# L6203.net
KiCad netlist of a schematic drawn in Altium Designer
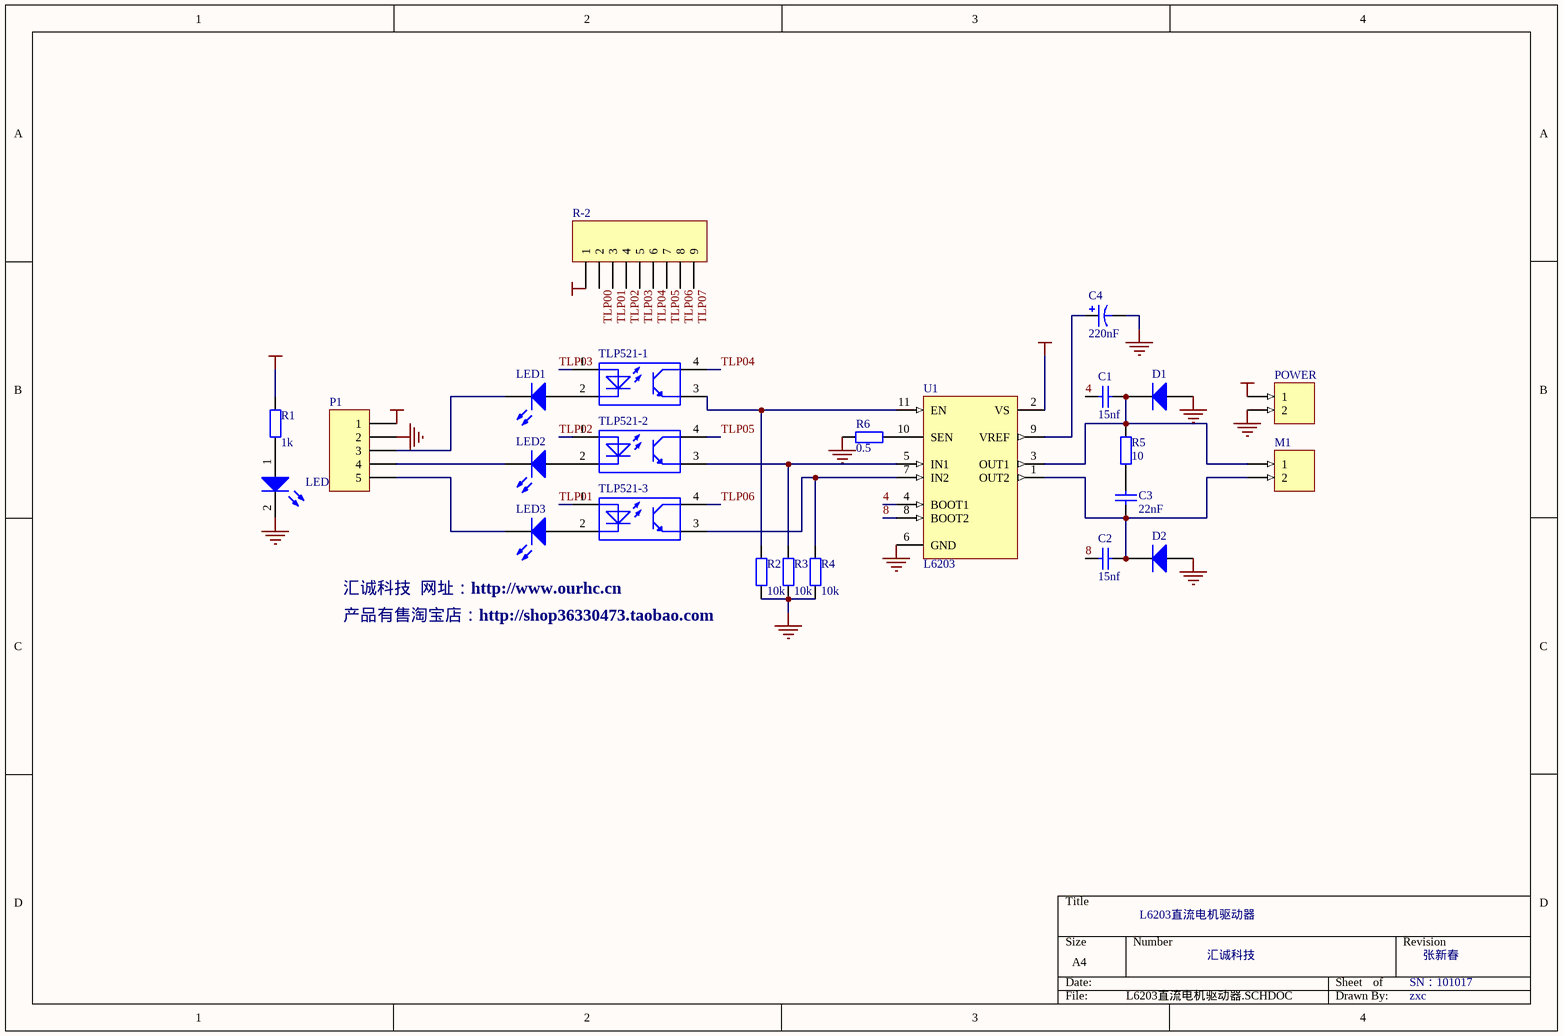
[diagram p0: L6203直流电机驱动器.SCHDOC]

(export (version "E")
  (design (tool "Eeschema 10.0.6"))
  (components
    (comp (ref "C1")
      (value "15nf")
      (footprint "CPDR")
      (description "Capacitor")
      (fields (field (name "PUBLISHER") "Altium Limited"))
      (libsource (lib "Miscellaneous Devices") (part "Cap"))
    )
    (comp (ref "C2")
      (value "15nf")
      (footprint "CPDR")
      (description "Capacitor")
      (fields (field (name "PUBLISHER") "Altium Limited"))
      (libsource (lib "Miscellaneous Devices") (part "Cap"))
    )
    (comp (ref "C3")
      (value "22nF")
      (footprint "CPDR")
      (description "Capacitor")
      (fields (field (name "PUBLISHER") "Altium Limited"))
      (libsource (lib "Miscellaneous Devices") (part "Cap"))
    )
    (comp (ref "C4")
      (value "220nF")
      (footprint "C-DJ-4")
      (description "Polarized Capacitor (Surface Mount)")
      (fields (field (name "PUBLISHER") "Altium Limited"))
      (libsource (lib "Miscellaneous Devices") (part "Cap Pol3"))
    )
    (comp (ref "D1")
      (value "1N4007")
      (footprint "ZCDZL")
      (description "1 Amp General Purpose Rectifier")
      (fields (field (name "PUBLISHER") "Altium Limited"))
      (libsource (lib "Miscellaneous Devices") (part "Diode 1N4007"))
    )
    (comp (ref "D2")
      (value "1N4007")
      (footprint "ZCDZL")
      (description "1 Amp General Purpose Rectifier")
      (fields (field (name "PUBLISHER") "Altium Limited"))
      (libsource (lib "Miscellaneous Devices") (part "Diode 1N4007"))
    )
    (comp (ref "LED")
      (value "LED")
      (footprint "CPDR")
      (description "发光二极管")
      (fields (field (name "PUBLISHER") "Altium Limited"))
      (libsource (lib "zxcourhc") (part "LED"))
    )
    (comp (ref "LED1")
      (value "~")
      (footprint "HDR1X2")
      (description "Typical BLUE SiC LED")
      (fields (field (name "PUBLISHER") "Altium Limited"))
      (libsource (lib "Miscellaneous Devices") (part "LED3"))
    )
    (comp (ref "LED2")
      (value "~")
      (footprint "HDR1X2")
      (description "Typical BLUE SiC LED")
      (fields (field (name "PUBLISHER") "Altium Limited"))
      (libsource (lib "Miscellaneous Devices") (part "LED3"))
    )
    (comp (ref "LED3")
      (value "~")
      (footprint "HDR1X2")
      (description "Typical BLUE SiC LED")
      (fields (field (name "PUBLISHER") "Altium Limited"))
      (libsource (lib "Miscellaneous Devices") (part "LED3"))
    )
    (comp (ref "M1")
      (value "~")
      (footprint "JK128_2")
      (description "Header, 2-Pin")
      (fields (field (name "PUBLISHER") "Altium Limited"))
      (libsource (lib "Miscellaneous Connectors") (part "MHDR1X2"))
    )
    (comp (ref "P1")
      (value "PZ_5")
      (footprint "HDR-5")
      (description "排针——5")
      (fields (field (name "PUBLISHER") "Altium Limited"))
      (libsource (lib "zxcourhc") (part "PZ_5"))
    )
    (comp (ref "POWER")
      (value "~")
      (footprint "JK128_2")
      (description "Header, 2-Pin")
      (fields (field (name "PUBLISHER") "Altium Limited"))
      (libsource (lib "Miscellaneous Connectors") (part "MHDR1X2"))
    )
    (comp (ref "R-2")
      (value "~")
      (footprint "HDR1X9")
      (description "Header, 9-Pin")
      (fields (field (name "PUBLISHER") "Altium Limited"))
      (libsource (lib "Miscellaneous Connectors") (part "Header 9"))
    )
    (comp (ref "R1")
      (value "1k")
      (footprint "zxcourhc:TP-0805-R")
      (description "电阻")
      (fields (field (name "Comment") "Res") (field (name "PUBLISHER") "Altium Limited"))
      (libsource (lib "zxcourhc") (part "Res"))
    )
    (comp (ref "R2")
      (value "10k")
      (footprint "zxcourhc:TP-0805-R")
      (description "电阻")
      (fields (field (name "Comment") "Res") (field (name "PUBLISHER") "Altium Limited"))
      (libsource (lib "zxcourhc") (part "Res"))
    )
    (comp (ref "R3")
      (value "10k")
      (footprint "zxcourhc:TP-0805-R")
      (description "电阻")
      (fields (field (name "Comment") "Res") (field (name "PUBLISHER") "Altium Limited"))
      (libsource (lib "zxcourhc") (part "Res"))
    )
    (comp (ref "R4")
      (value "10k")
      (footprint "zxcourhc:TP-0805-R")
      (description "电阻")
      (fields (field (name "Comment") "Res") (field (name "PUBLISHER") "Altium Limited"))
      (libsource (lib "zxcourhc") (part "Res"))
    )
    (comp (ref "R5")
      (value "10")
      (footprint "ZCDZL")
      (description "电阻")
      (fields (field (name "Comment") "Res") (field (name "PUBLISHER") "Altium Limited"))
      (libsource (lib "zxcourhc") (part "Res"))
    )
    (comp (ref "R6")
      (value "0.5")
      (footprint "ZCDZL")
      (description "电阻")
      (fields (field (name "Comment") "Res") (field (name "PUBLISHER") "Altium Limited"))
      (libsource (lib "") (part "Res_1"))
    )
    (comp (ref "TLP521-1") (value "~") (footprint "DIP-4") (libsource (lib "MyInt_Lib") (part "TLP521-1")))
    (comp (ref "TLP521-2") (value "~") (footprint "DIP-4") (libsource (lib "MyInt_Lib") (part "TLP521-1")))
    (comp (ref "TLP521-3") (value "~") (footprint "DIP-4") (libsource (lib "MyInt_Lib") (part "TLP521-1")))
    (comp (ref "U1")
      (value "L6203")
      (footprint "LMD18200")
      (description "DMOS Full Bridge Driver")
      (fields (field (name "PUBLISHER") "Altium Limited"))
      (libsource (lib "ST Interface DC Motor Controller") (part "L6203"))
    )
  )
  (nets
    (net (code "1") (name "+5V") (class "Default")
      (node (ref "P1") (pin "1") (pinfunction "1_1") (pintype "passive"))
      (node (ref "R-2") (pin "1") (pinfunction "1_1") (pintype "passive"))
      (node (ref "R1") (pin "1") (pinfunction "1_1") (pintype "passive"))
    )
    (net (code "2") (name "/4") (class "Default")
      (node (ref "C1") (pin "2") (pinfunction "2_2") (pintype "passive"))
      (node (ref "U1") (pin "4") (pinfunction "BOOT1_4") (pintype "input"))
    )
    (net (code "3") (name "/8") (class "Default")
      (node (ref "C2") (pin "2") (pinfunction "2_2") (pintype "passive"))
      (node (ref "U1") (pin "8") (pinfunction "BOOT2_8") (pintype "input"))
    )
    (net (code "4") (name "/TLP00") (class "Default")
      (node (ref "R-2") (pin "2") (pinfunction "2_2") (pintype "passive"))
    )
    (net (code "5") (name "/TLP01") (class "Default")
      (node (ref "R-2") (pin "3") (pinfunction "3_3") (pintype "passive"))
      (node (ref "TLP521-3") (pin "1") (pinfunction "1_1") (pintype "passive"))
    )
    (net (code "6") (name "/TLP02") (class "Default")
      (node (ref "R-2") (pin "4") (pinfunction "4_4") (pintype "passive"))
      (node (ref "TLP521-2") (pin "1") (pinfunction "1_1") (pintype "passive"))
    )
    (net (code "7") (name "/TLP03") (class "Default")
      (node (ref "R-2") (pin "5") (pinfunction "5_5") (pintype "passive"))
      (node (ref "TLP521-1") (pin "1") (pinfunction "1_1") (pintype "passive"))
    )
    (net (code "8") (name "/TLP04") (class "Default")
      (node (ref "R-2") (pin "6") (pinfunction "6_6") (pintype "passive"))
      (node (ref "TLP521-1") (pin "4") (pinfunction "4_4") (pintype "passive"))
    )
    (net (code "9") (name "/TLP05") (class "Default")
      (node (ref "R-2") (pin "7") (pinfunction "7_7") (pintype "passive"))
      (node (ref "TLP521-2") (pin "4") (pinfunction "4_4") (pintype "passive"))
    )
    (net (code "10") (name "/TLP06") (class "Default")
      (node (ref "R-2") (pin "8") (pinfunction "8_8") (pintype "passive"))
      (node (ref "TLP521-3") (pin "4") (pinfunction "4_4") (pintype "passive"))
    )
    (net (code "11") (name "/TLP07") (class "Default")
      (node (ref "R-2") (pin "9") (pinfunction "9_9") (pintype "passive"))
    )
    (net (code "12") (name "GND") (class "Default")
      (node (ref "C4") (pin "2") (pinfunction "2_2") (pintype "passive"))
      (node (ref "D1") (pin "1") (pinfunction "A_1") (pintype "passive"))
      (node (ref "D2") (pin "1") (pinfunction "A_1") (pintype "passive"))
      (node (ref "LED") (pin "2") (pinfunction "K_2") (pintype "passive"))
      (node (ref "P1") (pin "2") (pinfunction "2_2") (pintype "passive"))
      (node (ref "POWER") (pin "2") (pinfunction "2_2") (pintype "input"))
      (node (ref "R2") (pin "2") (pinfunction "2_2") (pintype "passive"))
      (node (ref "R3") (pin "2") (pinfunction "2_2") (pintype "passive"))
      (node (ref "R4") (pin "2") (pinfunction "2_2") (pintype "passive"))
      (node (ref "R6") (pin "1") (pinfunction "1_1") (pintype "passive"))
      (node (ref "U1") (pin "6") (pinfunction "GND_6") (pintype "power_in"))
    )
    (net (code "13") (name "Net-(C3-Pad1)") (class "Default")
      (node (ref "C3") (pin "1") (pinfunction "1_1") (pintype "passive"))
      (node (ref "R5") (pin "2") (pinfunction "2_2") (pintype "passive"))
    )
    (net (code "14") (name "Net-(D1-K)") (class "Default")
      (node (ref "C1") (pin "1") (pinfunction "1_1") (pintype "passive"))
      (node (ref "D1") (pin "2") (pinfunction "K_2") (pintype "passive"))
      (node (ref "M1") (pin "1") (pinfunction "1_1") (pintype "input"))
      (node (ref "R5") (pin "1") (pinfunction "1_1") (pintype "passive"))
      (node (ref "U1") (pin "3") (pinfunction "OUT1_3") (pintype "output"))
    )
    (net (code "15") (name "Net-(D2-K)") (class "Default")
      (node (ref "C2") (pin "1") (pinfunction "1_1") (pintype "passive"))
      (node (ref "C3") (pin "2") (pinfunction "2_2") (pintype "passive"))
      (node (ref "D2") (pin "2") (pinfunction "K_2") (pintype "passive"))
      (node (ref "M1") (pin "2") (pinfunction "2_2") (pintype "input"))
      (node (ref "U1") (pin "1") (pinfunction "OUT2_1") (pintype "output"))
    )
    (net (code "16") (name "Net-(LED-A)") (class "Default")
      (node (ref "LED") (pin "1") (pinfunction "A_1") (pintype "passive"))
      (node (ref "R1") (pin "2") (pinfunction "2_2") (pintype "passive"))
    )
    (net (code "17") (name "Net-(LED1-A)") (class "Default")
      (node (ref "LED1") (pin "1") (pinfunction "A_1") (pintype "passive"))
      (node (ref "TLP521-1") (pin "2") (pinfunction "2_2") (pintype "passive"))
    )
    (net (code "18") (name "Net-(LED1-K)") (class "Default")
      (node (ref "LED1") (pin "2") (pinfunction "K_2") (pintype "passive"))
      (node (ref "P1") (pin "3") (pinfunction "3_3") (pintype "passive"))
    )
    (net (code "19") (name "Net-(LED2-A)") (class "Default")
      (node (ref "LED2") (pin "1") (pinfunction "A_1") (pintype "passive"))
      (node (ref "TLP521-2") (pin "2") (pinfunction "2_2") (pintype "passive"))
    )
    (net (code "20") (name "Net-(LED2-K)") (class "Default")
      (node (ref "LED2") (pin "2") (pinfunction "K_2") (pintype "passive"))
      (node (ref "P1") (pin "4") (pinfunction "4_4") (pintype "passive"))
    )
    (net (code "21") (name "Net-(LED3-A)") (class "Default")
      (node (ref "LED3") (pin "1") (pinfunction "A_1") (pintype "passive"))
      (node (ref "TLP521-3") (pin "2") (pinfunction "2_2") (pintype "passive"))
    )
    (net (code "22") (name "Net-(LED3-K)") (class "Default")
      (node (ref "LED3") (pin "2") (pinfunction "K_2") (pintype "passive"))
      (node (ref "P1") (pin "5") (pinfunction "5_5") (pintype "passive"))
    )
    (net (code "23") (name "Net-(U1-EN)") (class "Default")
      (node (ref "R2") (pin "1") (pinfunction "1_1") (pintype "passive"))
      (node (ref "TLP521-1") (pin "3") (pinfunction "3_3") (pintype "passive"))
      (node (ref "U1") (pin "11") (pinfunction "EN_11") (pintype "input"))
    )
    (net (code "24") (name "Net-(U1-IN1)") (class "Default")
      (node (ref "R3") (pin "1") (pinfunction "1_1") (pintype "passive"))
      (node (ref "TLP521-2") (pin "3") (pinfunction "3_3") (pintype "passive"))
      (node (ref "U1") (pin "5") (pinfunction "IN1_5") (pintype "input"))
    )
    (net (code "25") (name "Net-(U1-IN2)") (class "Default")
      (node (ref "R4") (pin "1") (pinfunction "1_1") (pintype "passive"))
      (node (ref "TLP521-3") (pin "3") (pinfunction "3_3") (pintype "passive"))
      (node (ref "U1") (pin "7") (pinfunction "IN2_7") (pintype "input"))
    )
    (net (code "26") (name "Net-(U1-SEN)") (class "Default")
      (node (ref "R6") (pin "2") (pinfunction "2_2") (pintype "passive"))
      (node (ref "U1") (pin "10") (pinfunction "SEN_10") (pintype "passive"))
    )
    (net (code "27") (name "Net-(U1-VREF)") (class "Default")
      (node (ref "C4") (pin "1") (pinfunction "1_1") (pintype "passive"))
      (node (ref "U1") (pin "9") (pinfunction "VREF_9") (pintype "output"))
    )
    (net (code "28") (name "Vss") (class "Default")
      (node (ref "POWER") (pin "1") (pinfunction "1_1") (pintype "input"))
      (node (ref "U1") (pin "2") (pinfunction "VS_2") (pintype "power_in"))
    )
  )
)
